# CAN.net
KiCad netlist of a schematic drawn in Altium Designer
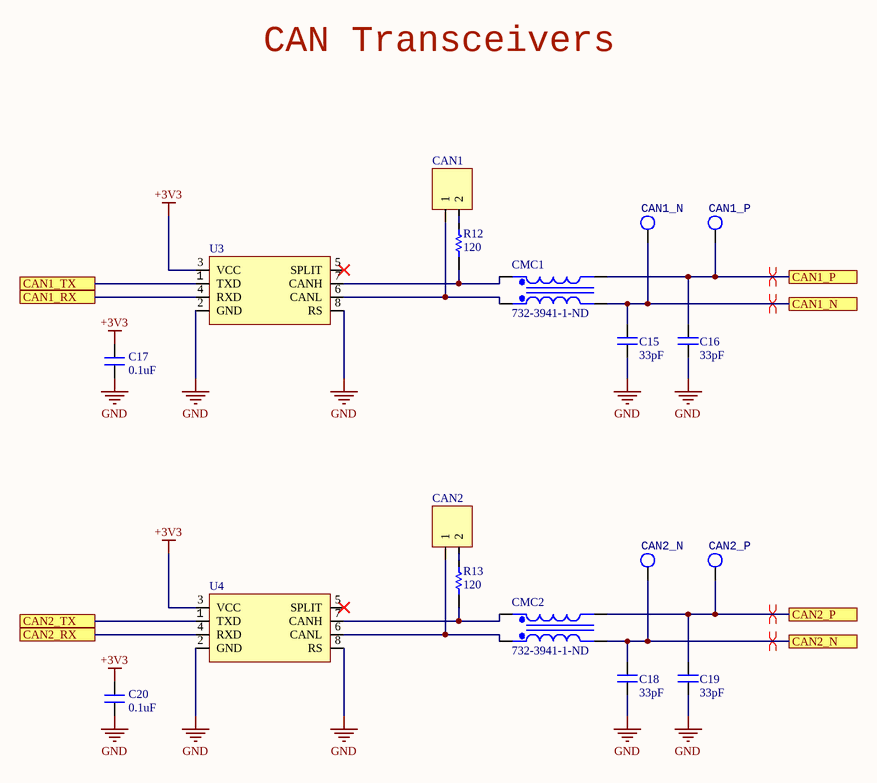
[diagram p0: CAN.SchDoc]

(export (version "E")
  (design (tool "Eeschema 10.0.6"))
  (components
    (comp (ref "C15")
      (value "CAP_33pF_50V_0603")
      (footprint "CAPC0603(1608)55_N")
      (description "CAP CER 33PF 50V C0G/NP0")
      (fields
        (field (name "VOLTAGE") "50V")
        (field (name "TOLERANCE") "5%")
        (field (name "CAPACITANCE") "33pF")
      )
      (libsource (lib "UWRT_Schematic_Library_2020") (part "CAP_33pF_50V_0603"))
    )
    (comp (ref "C16")
      (value "CAP_33pF_50V_0603")
      (footprint "CAPC0603(1608)55_N")
      (description "CAP CER 33PF 50V C0G/NP0")
      (fields
        (field (name "VOLTAGE") "50V")
        (field (name "TOLERANCE") "5%")
        (field (name "CAPACITANCE") "33pF")
      )
      (libsource (lib "UWRT_Schematic_Library_2020") (part "CAP_33pF_50V_0603"))
    )
    (comp (ref "C17")
      (value "0.1uF")
      (footprint "CAPC0603(1608)55_N")
      (description "CAP CER 0.1UF 16V X7R 0603")
      (fields (field (name "Comment") "CAP_0.1uF_16V_0603"))
      (libsource (lib "UWRT_Schematic_Library_2020") (part "CAP_0.1uF_16V_0603"))
    )
    (comp (ref "C18")
      (value "CAP_33pF_50V_0603")
      (footprint "CAPC0603(1608)55_N")
      (description "CAP CER 33PF 50V C0G/NP0")
      (fields
        (field (name "VOLTAGE") "50V")
        (field (name "TOLERANCE") "5%")
        (field (name "CAPACITANCE") "33pF")
      )
      (libsource (lib "UWRT_Schematic_Library_2020") (part "CAP_33pF_50V_0603"))
    )
    (comp (ref "C19")
      (value "CAP_33pF_50V_0603")
      (footprint "CAPC0603(1608)55_N")
      (description "CAP CER 33PF 50V C0G/NP0")
      (fields
        (field (name "VOLTAGE") "50V")
        (field (name "TOLERANCE") "5%")
        (field (name "CAPACITANCE") "33pF")
      )
      (libsource (lib "UWRT_Schematic_Library_2020") (part "CAP_33pF_50V_0603"))
    )
    (comp (ref "C20")
      (value "0.1uF")
      (footprint "CAPC0603(1608)55_N")
      (description "CAP CER 0.1UF 16V X7R 0603")
      (fields (field (name "Comment") "CAP_0.1uF_16V_0603"))
      (libsource (lib "UWRT_Schematic_Library_2020") (part "CAP_0.1uF_16V_0603"))
    )
    (comp (ref "CAN1")
      (value "JUMPER_2")
      (footprint "HDR1X2")
      (description "HEADER 2X1")
      (libsource (lib "UWRT_Schematic_Library_2020") (part "JUMPER_2"))
    )
    (comp (ref "CAN1_N")
      (value "TESTPOINT_LOOP")
      (footprint "TESTPOINT_LOOP")
      (description "Loop testpoint through-hole pad")
      (libsource (lib "UWRT_Schematic_Library_2020") (part "TESTPOINT_LOOP"))
    )
    (comp (ref "CAN1_P")
      (value "TESTPOINT_LOOP")
      (footprint "TESTPOINT_LOOP")
      (description "Loop testpoint through-hole pad")
      (libsource (lib "UWRT_Schematic_Library_2020") (part "TESTPOINT_LOOP"))
    )
    (comp (ref "CAN2")
      (value "JUMPER_2")
      (footprint "HDR1X2")
      (description "HEADER 2X1")
      (libsource (lib "UWRT_Schematic_Library_2020") (part "JUMPER_2"))
    )
    (comp (ref "CAN2_N")
      (value "TESTPOINT_LOOP")
      (footprint "TESTPOINT_LOOP")
      (description "Loop testpoint through-hole pad")
      (libsource (lib "UWRT_Schematic_Library_2020") (part "TESTPOINT_LOOP"))
    )
    (comp (ref "CAN2_P")
      (value "TESTPOINT_LOOP")
      (footprint "TESTPOINT_LOOP")
      (description "Loop testpoint through-hole pad")
      (libsource (lib "UWRT_Schematic_Library_2020") (part "TESTPOINT_LOOP"))
    )
    (comp (ref "CMC1")
      (value "CMC_51uH")
      (footprint "744212510")
      (description "CMC 51uH 300MA 2LN SMD")
      (fields (field (name "TOLERANCE") "50%") (field (name "SUPPLIER PART NUMBER 1") "732-3941-1-ND"))
      (libsource (lib "UWRT_Schematic_Library_2020") (part "CMC_51uH"))
    )
    (comp (ref "CMC2")
      (value "CMC_51uH")
      (footprint "744212510")
      (description "CMC 51uH 300MA 2LN SMD")
      (fields (field (name "TOLERANCE") "50%") (field (name "SUPPLIER PART NUMBER 1") "732-3941-1-ND"))
      (libsource (lib "UWRT_Schematic_Library_2020") (part "CMC_51uH"))
    )
    (comp (ref "R12")
      (value "120")
      (footprint "RESC0603(1608)_N")
      (description "RES SMD 120 OHM 5% 1/10W 0603")
      (fields (field (name "TOLERANCE") "5%") (field (name "Comment") "RES_120R_0603"))
      (libsource (lib "UWRT_Schematic_Library_2020") (part "RES_120R_0603"))
    )
    (comp (ref "R13")
      (value "120")
      (footprint "RESC0603(1608)_N")
      (description "RES SMD 120 OHM 5% 1/10W 0603")
      (fields (field (name "TOLERANCE") "5%") (field (name "Comment") "RES_120R_0603"))
      (libsource (lib "UWRT_Schematic_Library_2020") (part "RES_120R_0603"))
    )
    (comp (ref "U3")
      (value "IC TXRX CAN")
      (footprint "LT-S8_N")
      (description "IC TXRX CAN 4MBPS 8SO")
      (libsource (lib "UWRT_Schematic_Library_2020") (part "LTC2875"))
    )
    (comp (ref "U4")
      (value "IC TXRX CAN")
      (footprint "LT-S8_N")
      (description "IC TXRX CAN 4MBPS 8SO")
      (libsource (lib "UWRT_Schematic_Library_2020") (part "LTC2875"))
    )
  )
  (nets
    (net (code "1") (name "+3V3") (class "Default")
      (node (ref "C17") (pin "1") (pinfunction "1_1") (pintype "passive"))
      (node (ref "C20") (pin "1") (pinfunction "1_1") (pintype "passive"))
      (node (ref "U3") (pin "3") (pinfunction "VCC_3") (pintype "passive"))
      (node (ref "U4") (pin "3") (pinfunction "VCC_3") (pintype "passive"))
    )
    (net (code "2") (name "/CAN1_N") (class "Default")
      (node (ref "C15") (pin "2") (pinfunction "2_2") (pintype "passive"))
      (node (ref "CAN1_N") (pin "1") (pintype "passive"))
      (node (ref "CMC1") (pin "5") (pinfunction "Pri-_5") (pintype "passive"))
    )
    (net (code "3") (name "/CAN1_P") (class "Default")
      (node (ref "C16") (pin "2") (pinfunction "2_2") (pintype "passive"))
      (node (ref "CAN1_P") (pin "1") (pintype "passive"))
      (node (ref "CMC1") (pin "4") (pinfunction "Sec-_4") (pintype "passive"))
    )
    (net (code "4") (name "/CAN1_RX") (class "Default")
      (node (ref "U3") (pin "4") (pinfunction "RXD_4") (pintype "passive"))
    )
    (net (code "5") (name "/CAN1_TX") (class "Default")
      (node (ref "U3") (pin "1") (pinfunction "TXD_1") (pintype "passive"))
    )
    (net (code "6") (name "/CAN2_N") (class "Default")
      (node (ref "C18") (pin "2") (pinfunction "2_2") (pintype "passive"))
      (node (ref "CAN2_N") (pin "1") (pintype "passive"))
      (node (ref "CMC2") (pin "5") (pinfunction "Pri-_5") (pintype "passive"))
    )
    (net (code "7") (name "/CAN2_P") (class "Default")
      (node (ref "C19") (pin "2") (pinfunction "2_2") (pintype "passive"))
      (node (ref "CAN2_P") (pin "1") (pintype "passive"))
      (node (ref "CMC2") (pin "4") (pinfunction "Sec-_4") (pintype "passive"))
    )
    (net (code "8") (name "/CAN2_RX") (class "Default")
      (node (ref "U4") (pin "4") (pinfunction "RXD_4") (pintype "passive"))
    )
    (net (code "9") (name "/CAN2_TX") (class "Default")
      (node (ref "U4") (pin "1") (pinfunction "TXD_1") (pintype "passive"))
    )
    (net (code "10") (name "GND") (class "Default")
      (node (ref "C15") (pin "1") (pinfunction "1_1") (pintype "passive"))
      (node (ref "C16") (pin "1") (pinfunction "1_1") (pintype "passive"))
      (node (ref "C17") (pin "2") (pinfunction "2_2") (pintype "passive"))
      (node (ref "C18") (pin "1") (pinfunction "1_1") (pintype "passive"))
      (node (ref "C19") (pin "1") (pinfunction "1_1") (pintype "passive"))
      (node (ref "C20") (pin "2") (pinfunction "2_2") (pintype "passive"))
      (node (ref "U3") (pin "2") (pinfunction "GND_2") (pintype "passive"))
      (node (ref "U3") (pin "8") (pinfunction "RS_8") (pintype "passive"))
      (node (ref "U4") (pin "2") (pinfunction "GND_2") (pintype "passive"))
      (node (ref "U4") (pin "8") (pinfunction "RS_8") (pintype "passive"))
    )
    (net (code "11") (name "Net-(CAN1-Pad2)") (class "Default")
      (node (ref "CAN1") (pin "2") (pinfunction "2_2") (pintype "passive"))
      (node (ref "R12") (pin "1") (pinfunction "1_1") (pintype "passive"))
    )
    (net (code "12") (name "Net-(CAN2-Pad2)") (class "Default")
      (node (ref "CAN2") (pin "2") (pinfunction "2_2") (pintype "passive"))
      (node (ref "R13") (pin "1") (pinfunction "1_1") (pintype "passive"))
    )
    (net (code "13") (name "Net-(CMC1-Pri+)") (class "Default")
      (node (ref "CAN1") (pin "1") (pinfunction "1_1") (pintype "passive"))
      (node (ref "CMC1") (pin "1") (pinfunction "Pri+_1") (pintype "passive"))
      (node (ref "U3") (pin "6") (pinfunction "CANL_6") (pintype "passive"))
    )
    (net (code "14") (name "Net-(CMC1-Sec+)") (class "Default")
      (node (ref "CMC1") (pin "3") (pinfunction "Sec+_3") (pintype "passive"))
      (node (ref "R12") (pin "2") (pinfunction "2_2") (pintype "passive"))
      (node (ref "U3") (pin "7") (pinfunction "CANH_7") (pintype "passive"))
    )
    (net (code "15") (name "Net-(CMC2-Pri+)") (class "Default")
      (node (ref "CAN2") (pin "1") (pinfunction "1_1") (pintype "passive"))
      (node (ref "CMC2") (pin "1") (pinfunction "Pri+_1") (pintype "passive"))
      (node (ref "U4") (pin "6") (pinfunction "CANL_6") (pintype "passive"))
    )
    (net (code "16") (name "Net-(CMC2-Sec+)") (class "Default")
      (node (ref "CMC2") (pin "3") (pinfunction "Sec+_3") (pintype "passive"))
      (node (ref "R13") (pin "2") (pinfunction "2_2") (pintype "passive"))
      (node (ref "U4") (pin "7") (pinfunction "CANH_7") (pintype "passive"))
    )
    (net (code "17") (name "unconnected-(U3-SPLIT-Pad5)") (class "Default")
      (node (ref "U3") (pin "5") (pinfunction "SPLIT_5") (pintype "passive+no_connect"))
    )
    (net (code "18") (name "unconnected-(U4-SPLIT-Pad5)") (class "Default")
      (node (ref "U4") (pin "5") (pinfunction "SPLIT_5") (pintype "passive+no_connect"))
    )
  )
)
